# shield_horizontal_2.net
KiCad netlist of a schematic drawn in EAGLE
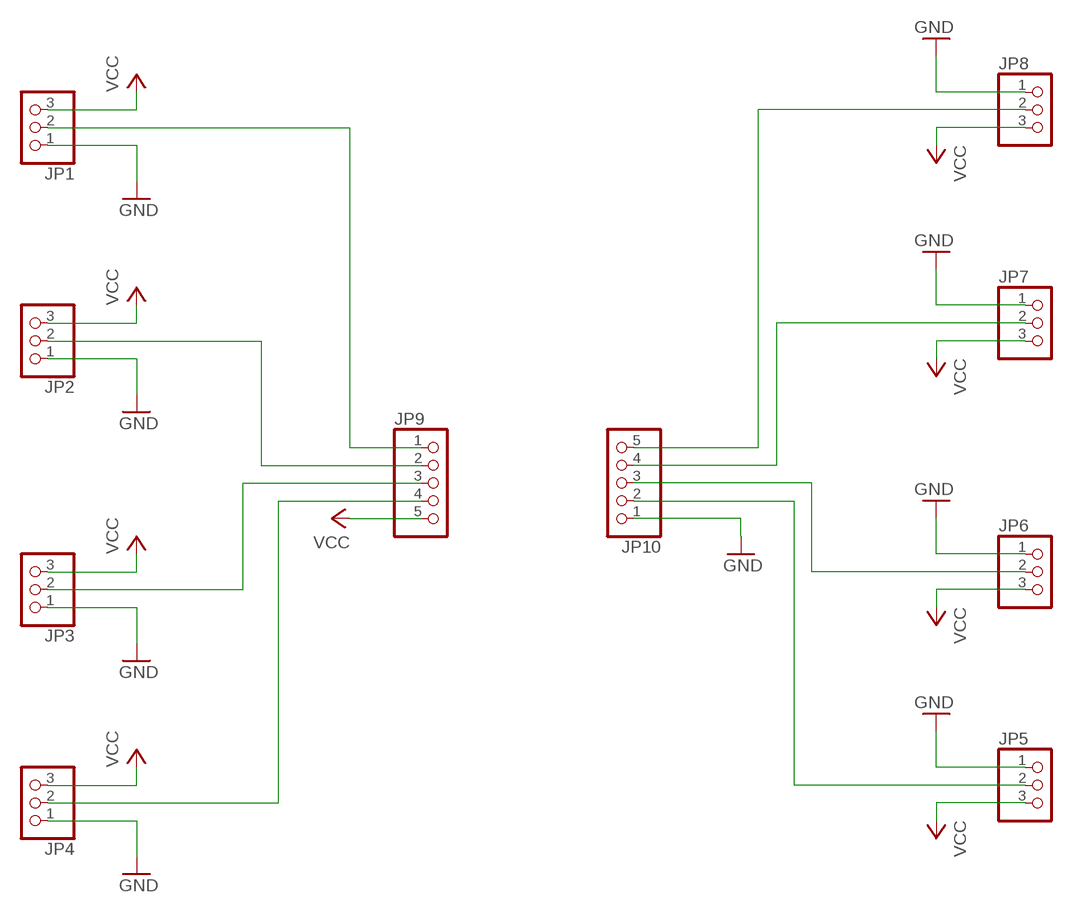
[diagram p0: schematic, sheet 1]

(export (version "E")
  (design (tool "Eeschema 10.0.6"))
  (components
    (comp (ref "JP1")
      (value "PINHD-1X3PS")
      (footprint "eagle-import:1X03-POTENTIOSHIELD")
      (libsource (lib "eagle-import") (part "PINHD-1X3PS"))
    )
    (comp (ref "JP2")
      (value "PINHD-1X3PS")
      (footprint "eagle-import:1X03-POTENTIOSHIELD")
      (libsource (lib "eagle-import") (part "PINHD-1X3PS"))
    )
    (comp (ref "JP3")
      (value "PINHD-1X3PS")
      (footprint "eagle-import:1X03-POTENTIOSHIELD")
      (libsource (lib "eagle-import") (part "PINHD-1X3PS"))
    )
    (comp (ref "JP4")
      (value "PINHD-1X3PS")
      (footprint "eagle-import:1X03-POTENTIOSHIELD")
      (libsource (lib "eagle-import") (part "PINHD-1X3PS"))
    )
    (comp (ref "JP5")
      (value "PINHD-1X3PS")
      (footprint "eagle-import:1X03-POTENTIOSHIELD")
      (libsource (lib "eagle-import") (part "PINHD-1X3PS"))
    )
    (comp (ref "JP6")
      (value "PINHD-1X3PS")
      (footprint "eagle-import:1X03-POTENTIOSHIELD")
      (libsource (lib "eagle-import") (part "PINHD-1X3PS"))
    )
    (comp (ref "JP7")
      (value "PINHD-1X3PS")
      (footprint "eagle-import:1X03-POTENTIOSHIELD")
      (libsource (lib "eagle-import") (part "PINHD-1X3PS"))
    )
    (comp (ref "JP8")
      (value "PINHD-1X3PS")
      (footprint "eagle-import:1X03-POTENTIOSHIELD")
      (libsource (lib "eagle-import") (part "PINHD-1X3PS"))
    )
    (comp (ref "JP9")
      (value "PINHD-1X5")
      (footprint "eagle-import:1X05")
      (libsource (lib "eagle-import") (part "PINHD-1X5"))
    )
    (comp (ref "JP10")
      (value "PINHD-1X5")
      (footprint "eagle-import:1X05")
      (libsource (lib "eagle-import") (part "PINHD-1X5"))
    )
  )
  (nets
    (net (code "1") (name "GND") (class "Default")
      (node (ref "JP1") (pin "1") (pinfunction "1_1") (pintype "passive"))
      (node (ref "JP10") (pin "1") (pinfunction "1_1") (pintype "passive"))
      (node (ref "JP2") (pin "1") (pinfunction "1_1") (pintype "passive"))
      (node (ref "JP3") (pin "1") (pinfunction "1_1") (pintype "passive"))
      (node (ref "JP4") (pin "1") (pinfunction "1_1") (pintype "passive"))
      (node (ref "JP5") (pin "1") (pinfunction "1_1") (pintype "passive"))
      (node (ref "JP6") (pin "1") (pinfunction "1_1") (pintype "passive"))
      (node (ref "JP7") (pin "1") (pinfunction "1_1") (pintype "passive"))
      (node (ref "JP8") (pin "1") (pinfunction "1_1") (pintype "passive"))
    )
    (net (code "2") (name "Net-(JP1-Pad2)") (class "Default")
      (node (ref "JP1") (pin "2") (pinfunction "2_2") (pintype "passive"))
      (node (ref "JP9") (pin "1") (pinfunction "1_1") (pintype "passive"))
    )
    (net (code "3") (name "Net-(JP2-Pad2)") (class "Default")
      (node (ref "JP2") (pin "2") (pinfunction "2_2") (pintype "passive"))
      (node (ref "JP9") (pin "2") (pinfunction "2_2") (pintype "passive"))
    )
    (net (code "4") (name "Net-(JP3-Pad2)") (class "Default")
      (node (ref "JP3") (pin "2") (pinfunction "2_2") (pintype "passive"))
      (node (ref "JP9") (pin "3") (pinfunction "3_3") (pintype "passive"))
    )
    (net (code "5") (name "Net-(JP4-Pad2)") (class "Default")
      (node (ref "JP4") (pin "2") (pinfunction "2_2") (pintype "passive"))
      (node (ref "JP9") (pin "4") (pinfunction "4_4") (pintype "passive"))
    )
    (net (code "6") (name "Net-(JP10-Pad2)") (class "Default")
      (node (ref "JP10") (pin "2") (pinfunction "2_2") (pintype "passive"))
      (node (ref "JP5") (pin "2") (pinfunction "2_2") (pintype "passive"))
    )
    (net (code "7") (name "Net-(JP10-Pad3)") (class "Default")
      (node (ref "JP10") (pin "3") (pinfunction "3_3") (pintype "passive"))
      (node (ref "JP6") (pin "2") (pinfunction "2_2") (pintype "passive"))
    )
    (net (code "8") (name "Net-(JP10-Pad4)") (class "Default")
      (node (ref "JP10") (pin "4") (pinfunction "4_4") (pintype "passive"))
      (node (ref "JP7") (pin "2") (pinfunction "2_2") (pintype "passive"))
    )
    (net (code "9") (name "Net-(JP10-Pad5)") (class "Default")
      (node (ref "JP10") (pin "5") (pinfunction "5_5") (pintype "passive"))
      (node (ref "JP8") (pin "2") (pinfunction "2_2") (pintype "passive"))
    )
    (net (code "10") (name "VCC") (class "Default")
      (node (ref "JP1") (pin "3") (pinfunction "3_3") (pintype "passive"))
      (node (ref "JP2") (pin "3") (pinfunction "3_3") (pintype "passive"))
      (node (ref "JP3") (pin "3") (pinfunction "3_3") (pintype "passive"))
      (node (ref "JP4") (pin "3") (pinfunction "3_3") (pintype "passive"))
      (node (ref "JP5") (pin "3") (pinfunction "3_3") (pintype "passive"))
      (node (ref "JP6") (pin "3") (pinfunction "3_3") (pintype "passive"))
      (node (ref "JP7") (pin "3") (pinfunction "3_3") (pintype "passive"))
      (node (ref "JP8") (pin "3") (pinfunction "3_3") (pintype "passive"))
      (node (ref "JP9") (pin "5") (pinfunction "5_5") (pintype "passive"))
    )
  )
)
